# PCB-PWR-2R-70-1_1-in-wall-IoT-Switch-Pow.net
KiCad netlist of a schematic drawn in EAGLE
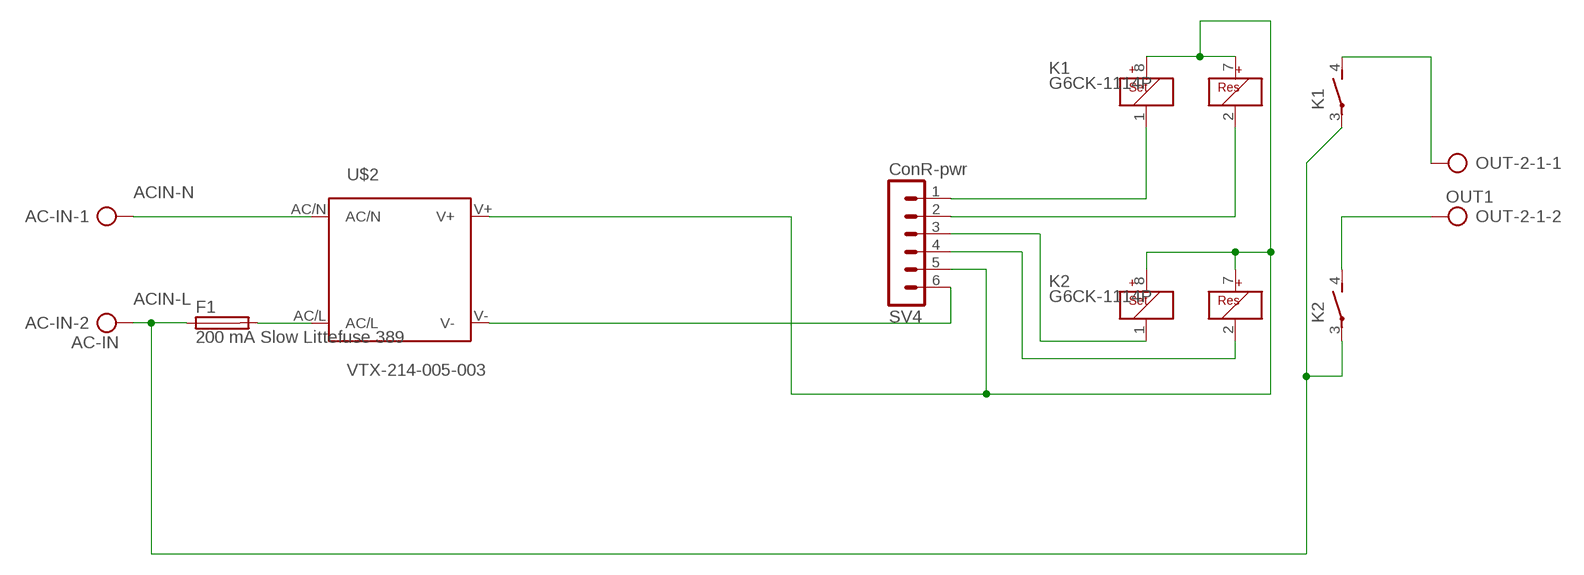
[diagram p0: schematic, sheet 1]

(export (version "E")
  (design (tool "Eeschema 10.0.6"))
  (components
    (comp (ref "AC-IN")
      (value "AC-IN")
      (footprint "eagle-import:AK500_2-H")
      (libsource (lib "eagle-import") (part "AK500/2-H"))
    )
    (comp (ref "F1")
      (value "200 mA Slow Littefuse 389")
      (footprint "eagle-import:TE5")
      (libsource (lib "eagle-import") (part "FUSETE5"))
    )
    (comp (ref "K1")
      (value "G6CK-1114P")
      (footprint "eagle-import:G6CK-1117P")
      (libsource (lib "eagle-import") (part "G6CK-1114P"))
    )
    (comp (ref "K2")
      (value "G6CK-1114P")
      (footprint "eagle-import:G6CK-1117P")
      (libsource (lib "eagle-import") (part "G6CK-1114P"))
    )
    (comp (ref "OUT-2-1")
      (value "OUT1")
      (footprint "eagle-import:AK500_2-H")
      (libsource (lib "eagle-import") (part "AK500/2-H"))
    )
    (comp (ref "SV4")
      (value "ConR-pwr")
      (footprint "eagle-import:MA06-1")
      (libsource (lib "eagle-import") (part "MA06-1"))
    )
    (comp (ref "U$2")
      (value "VTX-214-005-003")
      (footprint "eagle-import:VTX-214-005-003")
      (libsource (lib "eagle-import") (part "VTX-214-005-003"))
    )
  )
  (nets
    (net (code "1") (name "/ACIN-L") (class "Default")
      (node (ref "AC-IN") (pin "2") (pinfunction "KL_2") (pintype "passive"))
      (node (ref "F1") (pin "1") (pinfunction "1_1") (pintype "passive"))
      (node (ref "K1") (pin "3") (pinfunction "P_3") (pintype "passive"))
      (node (ref "K2") (pin "3") (pinfunction "P_3") (pintype "passive"))
    )
    (net (code "2") (name "/ACIN-N") (class "Default")
      (node (ref "AC-IN") (pin "1") (pinfunction "KL_1") (pintype "passive"))
      (node (ref "U$2") (pin "AC/N") (pinfunction "AC/N_AC/N") (pintype "input"))
    )
    (net (code "3") (name "Net-(F1-Pad2)") (class "Default")
      (node (ref "F1") (pin "2") (pinfunction "2_2") (pintype "passive"))
      (node (ref "U$2") (pin "AC/L") (pinfunction "AC/L_AC/L") (pintype "input"))
    )
    (net (code "4") (name "Net-(K1A-S)") (class "Default")
      (node (ref "K1") (pin "4") (pinfunction "S_4") (pintype "passive"))
      (node (ref "OUT-2-1") (pin "1") (pinfunction "KL_1") (pintype "passive"))
    )
    (net (code "5") (name "Net-(K1B-R+)") (class "Default")
      (node (ref "K1") (pin "7") (pinfunction "R+_7") (pintype "passive"))
      (node (ref "K1") (pin "8") (pinfunction "S+_8") (pintype "passive"))
      (node (ref "K2") (pin "7") (pinfunction "R+_7") (pintype "passive"))
      (node (ref "K2") (pin "8") (pinfunction "S+_8") (pintype "passive"))
      (node (ref "SV4") (pin "5") (pinfunction "5_5") (pintype "passive"))
      (node (ref "U$2") (pin "V+") (pinfunction "V+_V+") (pintype "output"))
    )
    (net (code "6") (name "Net-(K1B-R-)") (class "Default")
      (node (ref "K1") (pin "2") (pinfunction "R-_2") (pintype "passive"))
      (node (ref "SV4") (pin "2") (pinfunction "2_2") (pintype "passive"))
    )
    (net (code "7") (name "Net-(K1B-S-)") (class "Default")
      (node (ref "K1") (pin "1") (pinfunction "S-_1") (pintype "passive"))
      (node (ref "SV4") (pin "1") (pinfunction "1_1") (pintype "passive"))
    )
    (net (code "8") (name "Net-(K2A-S)") (class "Default")
      (node (ref "K2") (pin "4") (pinfunction "S_4") (pintype "passive"))
      (node (ref "OUT-2-1") (pin "2") (pinfunction "KL_2") (pintype "passive"))
    )
    (net (code "9") (name "Net-(K2B-R-)") (class "Default")
      (node (ref "K2") (pin "2") (pinfunction "R-_2") (pintype "passive"))
      (node (ref "SV4") (pin "4") (pinfunction "4_4") (pintype "passive"))
    )
    (net (code "10") (name "Net-(K2B-S-)") (class "Default")
      (node (ref "K2") (pin "1") (pinfunction "S-_1") (pintype "passive"))
      (node (ref "SV4") (pin "3") (pinfunction "3_3") (pintype "passive"))
    )
    (net (code "11") (name "Net-(SV4-Pad6)") (class "Default")
      (node (ref "SV4") (pin "6") (pinfunction "6_6") (pintype "passive"))
      (node (ref "U$2") (pin "V-") (pinfunction "V-_V-") (pintype "output"))
    )
  )
)
